# SAMR21_Xplained_Pro_Target_MCU.net
KiCad netlist of a schematic drawn in Altium Designer
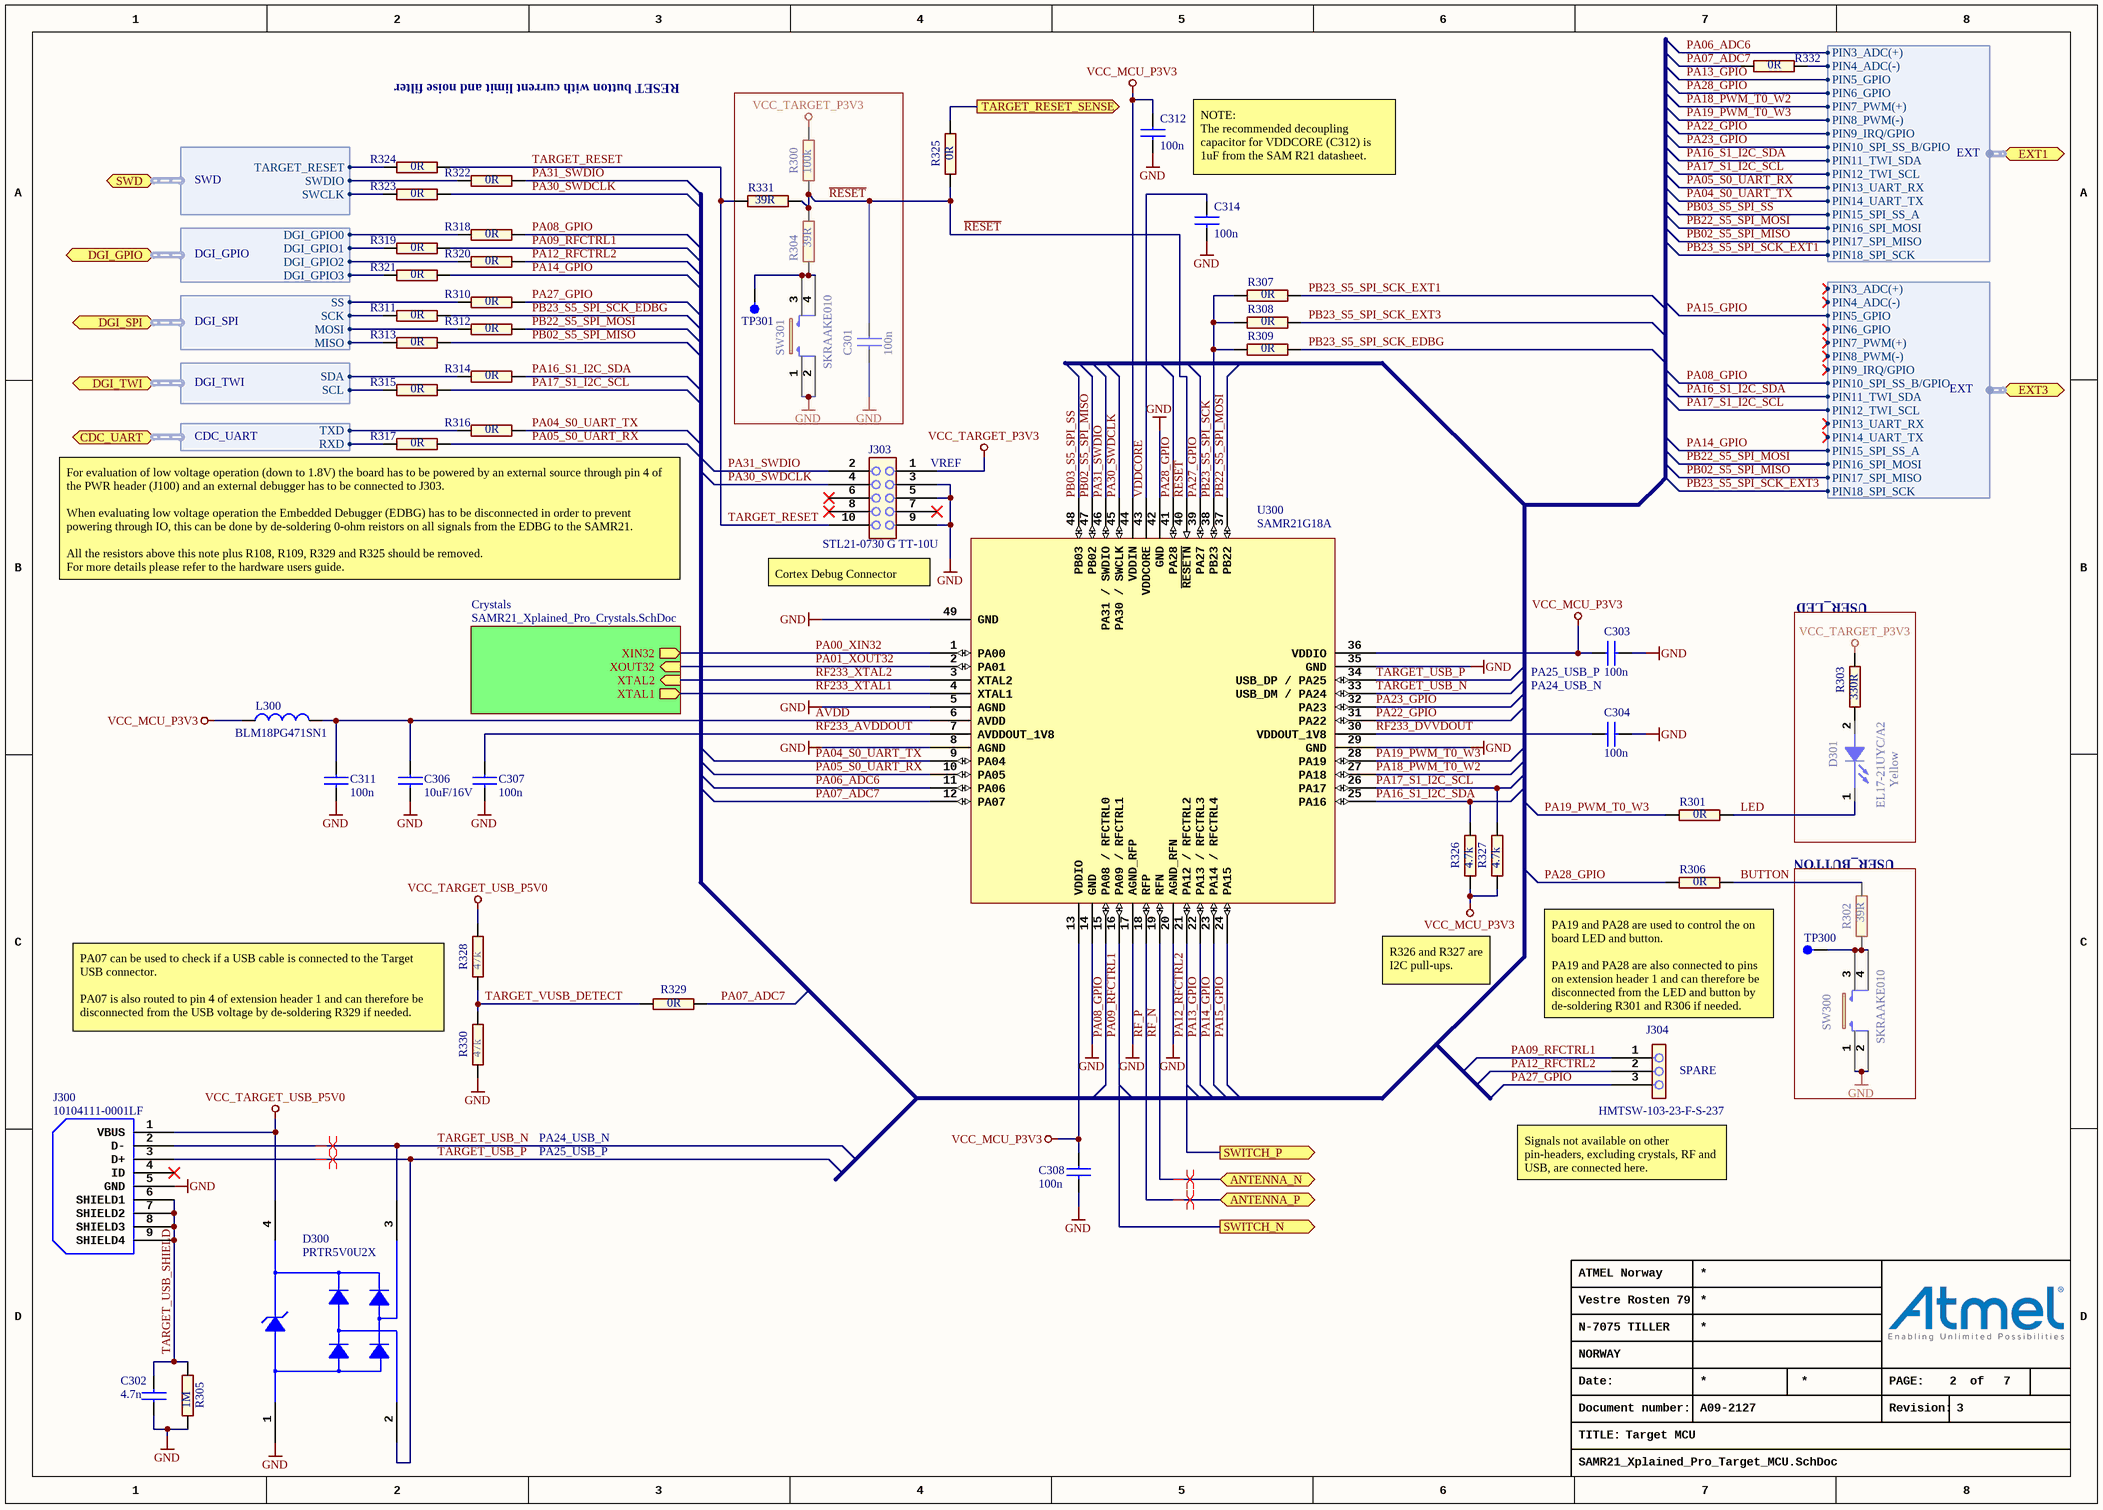
[diagram p0: SAMR21_Xplained_Pro_Target_MCU.SchDoc]

(export (version "E")
  (design (tool "Eeschema 10.0.6"))
  (components
    (comp (ref "C301")
      (value "100n")
      (footprint "AP1-00053")
      (description "Ceramic capacitor, SMD 0402, X7R, 16V, +/-10%")
      (fields (field (name "TOLERANCE") "16V, +/-10%") (field (name "MANUFACTURER") "Kemet"))
      (libsource (lib "AltiumDbLib") (part "CAP-NONPOL"))
    )
    (comp (ref "C302")
      (value "4.7n")
      (footprint "AP1-00053")
      (description "Ceramic capacitor, SMD 0402, X7R, 25V, +/-10%")
      (fields (field (name "TOLERANCE") "25V, +/-10%") (field (name "Comment") "CAP-NONPOL"))
      (libsource (lib "AltiumDbLib") (part "CAP-NONPOL"))
    )
    (comp (ref "C303")
      (value "100n")
      (footprint "AP1-00001")
      (description "Ceramic capacitor, SMD 0402, X7R, 16V, +/-10%")
      (fields (field (name "TOLERANCE") "16V, +/-10%") (field (name "MANUFACTURER") "Kemet"))
      (libsource (lib "AltiumDbLib") (part "CAP-NONPOL"))
    )
    (comp (ref "C304")
      (value "100n")
      (footprint "AP1-00001")
      (description "Ceramic capacitor, SMD 0402, X7R, 16V, +/-10%")
      (fields (field (name "TOLERANCE") "16V, +/-10%") (field (name "MANUFACTURER") "Kemet"))
      (libsource (lib "AltiumDbLib") (part "CAP-NONPOL"))
    )
    (comp (ref "C306")
      (value "10uF/16V")
      (footprint "AP1-00039")
      (description "Ceramic capacitor, SMD 0603, X5R, 16V, 10UF ± 20% (High Density)")
      (fields (field (name "MANUFACTURER") "Taiyo Yuden") (field (name "MPN") "EMK107BBJ106MA-T"))
      (libsource (lib "AltiumDbLib") (part "CAP-NONPOL"))
    )
    (comp (ref "C307")
      (value "100n")
      (footprint "AP1-00001")
      (description "Ceramic capacitor, SMD 0402, X7R, 16V, +/-10%")
      (fields (field (name "TOLERANCE") "16V, +/-10%") (field (name "MANUFACTURER") "Kemet"))
      (libsource (lib "AltiumDbLib") (part "CAP-NONPOL"))
    )
    (comp (ref "C308")
      (value "100n")
      (footprint "AP1-00001")
      (description "Ceramic capacitor, SMD 0402, X7R, 16V, +/-10%")
      (fields (field (name "TOLERANCE") "16V, +/-10%") (field (name "MANUFACTURER") "Kemet"))
      (libsource (lib "AltiumDbLib") (part "CAP-NONPOL"))
    )
    (comp (ref "C311")
      (value "100n")
      (footprint "AP1-00001")
      (description "Ceramic capacitor, SMD 0402, X7R, 16V, +/-10%")
      (fields (field (name "TOLERANCE") "16V, +/-10%") (field (name "MANUFACTURER") "Kemet"))
      (libsource (lib "AltiumDbLib") (part "CAP-NONPOL"))
    )
    (comp (ref "C312")
      (value "100n")
      (footprint "AP1-00001")
      (description "Ceramic capacitor, SMD 0402, X7R, 16V, +/-10%")
      (fields (field (name "TOLERANCE") "16V, +/-10%") (field (name "MANUFACTURER") "Kemet"))
      (libsource (lib "AltiumDbLib") (part "CAP-NONPOL"))
    )
    (comp (ref "C314")
      (value "100n")
      (footprint "AP1-00001")
      (description "Ceramic capacitor, SMD 0402, X7R, 16V, +/-10%")
      (fields (field (name "TOLERANCE") "16V, +/-10%") (field (name "MANUFACTURER") "Kemet"))
      (libsource (lib "AltiumDbLib") (part "CAP-NONPOL"))
    )
    (comp (ref "D300")
      (value "PRTR5V0U2X")
      (footprint "AP4-00001")
      (description "Double rail-to-rail USB ESD protection diode")
      (fields (field (name "MANUFACTURER") "Philips"))
      (libsource (lib "AltiumDbLib") (part "PRTR5V0U2X"))
    )
    (comp (ref "D301")
      (value "Yellow")
      (footprint "AP4-00013")
      (description "LED, Yellow, Wave length=591nm, SMD 0805, ±70°")
      (fields
        (field (name "ALTIUM_VALUE") "EL17-21UYC/A2")
        (field (name "MANUFACTURER") "Everlight")
        (field (name "MPN") "17-21UYC/S530-A3/TR8")
      )
      (libsource (lib "AltiumDbLib") (part "LED_12"))
    )
    (comp (ref "J300")
      (value "10104111-0001LF")
      (footprint "AP8-00604")
      (description "Micro USB AB Connector")
      (fields (field (name "MANUFACTURER") "FCI") (field (name "Comment") "USB_AB"))
      (libsource (lib "AltiumDbLib") (part "USB_AB"))
    )
    (comp (ref "J303")
      (value "HEADER 2x5")
      (footprint "AP8-00257")
      (description "2x5 pin header, 1.27mm pitch, THM")
      (fields (field (name "MANUFACTURER") "Garry") (field (name "MPN") "STL21-0730 G TT-10U"))
      (libsource (lib "AltiumDbLib") (part "HEADER 2x5"))
    )
    (comp (ref "J304")
      (value "HMTSW-103-23-F-S-237")
      (footprint "AP8-00745")
      (description "1x3 pin header, 2.54mm pitch, Pin-in-Paste THM, 1mm hole")
      (fields (field (name "Comment") "HEADER 1x3"))
      (libsource (lib "AltiumDbLib") (part "HEADER 1x3"))
    )
    (comp (ref "L300")
      (value "BLM18PG471SN1")
      (footprint "AP3-00005")
      (description "SMD RF inductor 0603. Z=470Ohm (@100MHz), Max R(dc)=0.65Ohm, Max current=1A")
      (fields (field (name "TOLERANCE") "±25%") (field (name "MANUFACTURER") "Murata"))
      (libsource (lib "AltiumDbLib") (part "INDUCTOR"))
    )
    (comp (ref "R300")
      (value "100k")
      (footprint "AP2-00000")
      (description "Thick film resistor, SMD 0402, 1/16W, 1%")
      (fields (field (name "TOLERANCE") "1 %") (field (name "Comment") "R2"))
      (libsource (lib "") (part "R2_1"))
    )
    (comp (ref "R301")
      (value "0R")
      (footprint "AP2-00000")
      (description "RES 0.0 OHM 1/16W 0402 SMD")
      (fields (field (name "TOLERANCE") "1 %") (field (name "MPN") "RMCF0402ZT0R00"))
      (libsource (lib "AltiumDbLib") (part "R2"))
    )
    (comp (ref "R302")
      (value "39R")
      (footprint "AP2-00011")
      (description "Thick film resistor, SMD 0402, 1/16W, 1%")
      (fields (field (name "TOLERANCE") "1 %") (field (name "Comment") "R2"))
      (libsource (lib "") (part "R2_3"))
    )
    (comp (ref "R303")
      (value "330R")
      (footprint "AP2-00000")
      (description "Thick film resistor, SMD 0402, 1/16W, 1%")
      (fields (field (name "TOLERANCE") "1 %") (field (name "Comment") "R2"))
      (libsource (lib "") (part "R2_1"))
    )
    (comp (ref "R304")
      (value "39R")
      (footprint "AP2-00011")
      (description "Thick film resistor, SMD 0402, 1/16W, 1%")
      (fields (field (name "TOLERANCE") "1 %") (field (name "Comment") "R2"))
      (libsource (lib "") (part "R2_3"))
    )
    (comp (ref "R305")
      (value "1M")
      (footprint "AP2-00011")
      (description "Thick film resistor, SMD 0402, 1/16W, 1%")
      (fields (field (name "TOLERANCE") "1 %") (field (name "MANUFACTURER") "KOA"))
      (libsource (lib "") (part "R2_3"))
    )
    (comp (ref "R306")
      (value "0R")
      (footprint "AP2-00000")
      (description "RES 0.0 OHM 1/16W 0402 SMD")
      (fields (field (name "TOLERANCE") "1 %") (field (name "MPN") "RMCF0402ZT0R00"))
      (libsource (lib "AltiumDbLib") (part "R2"))
    )
    (comp (ref "R307")
      (value "0R")
      (footprint "AP2-00000")
      (description "RES 0.0 OHM 1/16W 0402 SMD")
      (fields (field (name "TOLERANCE") "1 %") (field (name "MPN") "RMCF0402ZT0R00"))
      (libsource (lib "AltiumDbLib") (part "R2"))
    )
    (comp (ref "R308")
      (value "0R")
      (footprint "AP2-00000")
      (description "RES 0.0 OHM 1/16W 0402 SMD")
      (fields (field (name "TOLERANCE") "1 %") (field (name "MPN") "RMCF0402ZT0R00"))
      (libsource (lib "AltiumDbLib") (part "R2"))
    )
    (comp (ref "R309")
      (value "0R")
      (footprint "AP2-00000")
      (description "RES 0.0 OHM 1/16W 0402 SMD")
      (fields (field (name "TOLERANCE") "1 %") (field (name "MPN") "RMCF0402ZT0R00"))
      (libsource (lib "AltiumDbLib") (part "R2"))
    )
    (comp (ref "R310")
      (value "0R")
      (footprint "AP2-00000")
      (description "RES 0.0 OHM 1/16W 0402 SMD")
      (fields (field (name "TOLERANCE") "1 %") (field (name "MPN") "RMCF0402ZT0R00"))
      (libsource (lib "AltiumDbLib") (part "R2"))
    )
    (comp (ref "R311")
      (value "0R")
      (footprint "AP2-00000")
      (description "RES 0.0 OHM 1/16W 0402 SMD")
      (fields (field (name "TOLERANCE") "1 %") (field (name "MPN") "RMCF0402ZT0R00"))
      (libsource (lib "AltiumDbLib") (part "R2"))
    )
    (comp (ref "R312")
      (value "0R")
      (footprint "AP2-00000")
      (description "RES 0.0 OHM 1/16W 0402 SMD")
      (fields (field (name "TOLERANCE") "1 %") (field (name "MPN") "RMCF0402ZT0R00"))
      (libsource (lib "AltiumDbLib") (part "R2"))
    )
    (comp (ref "R313")
      (value "0R")
      (footprint "AP2-00000")
      (description "RES 0.0 OHM 1/16W 0402 SMD")
      (fields (field (name "TOLERANCE") "1 %") (field (name "MPN") "RMCF0402ZT0R00"))
      (libsource (lib "AltiumDbLib") (part "R2"))
    )
    (comp (ref "R314")
      (value "0R")
      (footprint "AP2-00000")
      (description "RES 0.0 OHM 1/16W 0402 SMD")
      (fields (field (name "TOLERANCE") "1 %") (field (name "MPN") "RMCF0402ZT0R00"))
      (libsource (lib "AltiumDbLib") (part "R2"))
    )
    (comp (ref "R315")
      (value "0R")
      (footprint "AP2-00000")
      (description "RES 0.0 OHM 1/16W 0402 SMD")
      (fields (field (name "TOLERANCE") "1 %") (field (name "MPN") "RMCF0402ZT0R00"))
      (libsource (lib "AltiumDbLib") (part "R2"))
    )
    (comp (ref "R316")
      (value "0R")
      (footprint "AP2-00000")
      (description "RES 0.0 OHM 1/16W 0402 SMD")
      (fields (field (name "TOLERANCE") "1 %") (field (name "MPN") "RMCF0402ZT0R00"))
      (libsource (lib "AltiumDbLib") (part "R2"))
    )
    (comp (ref "R317")
      (value "0R")
      (footprint "AP2-00000")
      (description "RES 0.0 OHM 1/16W 0402 SMD")
      (fields (field (name "TOLERANCE") "1 %") (field (name "MPN") "RMCF0402ZT0R00"))
      (libsource (lib "AltiumDbLib") (part "R2"))
    )
    (comp (ref "R318")
      (value "0R")
      (footprint "AP2-00000")
      (description "RES 0.0 OHM 1/16W 0402 SMD")
      (fields (field (name "TOLERANCE") "1 %") (field (name "MPN") "RMCF0402ZT0R00"))
      (libsource (lib "AltiumDbLib") (part "R2"))
    )
    (comp (ref "R319")
      (value "0R")
      (footprint "AP2-00000")
      (description "RES 0.0 OHM 1/16W 0402 SMD")
      (fields (field (name "TOLERANCE") "1 %") (field (name "MPN") "RMCF0402ZT0R00"))
      (libsource (lib "AltiumDbLib") (part "R2"))
    )
    (comp (ref "R320")
      (value "0R")
      (footprint "AP2-00000")
      (description "RES 0.0 OHM 1/16W 0402 SMD")
      (fields (field (name "TOLERANCE") "1 %") (field (name "MPN") "RMCF0402ZT0R00"))
      (libsource (lib "AltiumDbLib") (part "R2"))
    )
    (comp (ref "R321")
      (value "0R")
      (footprint "AP2-00000")
      (description "RES 0.0 OHM 1/16W 0402 SMD")
      (fields (field (name "TOLERANCE") "1 %") (field (name "MPN") "RMCF0402ZT0R00"))
      (libsource (lib "AltiumDbLib") (part "R2"))
    )
    (comp (ref "R322")
      (value "0R")
      (footprint "AP2-00000")
      (description "RES 0.0 OHM 1/16W 0402 SMD")
      (fields (field (name "TOLERANCE") "1 %") (field (name "MPN") "RMCF0402ZT0R00"))
      (libsource (lib "AltiumDbLib") (part "R2"))
    )
    (comp (ref "R323")
      (value "0R")
      (footprint "AP2-00000")
      (description "RES 0.0 OHM 1/16W 0402 SMD")
      (fields (field (name "TOLERANCE") "1 %") (field (name "MPN") "RMCF0402ZT0R00"))
      (libsource (lib "AltiumDbLib") (part "R2"))
    )
    (comp (ref "R324")
      (value "0R")
      (footprint "AP2-00000")
      (description "RES 0.0 OHM 1/16W 0402 SMD")
      (fields (field (name "TOLERANCE") "1 %") (field (name "MPN") "RMCF0402ZT0R00"))
      (libsource (lib "AltiumDbLib") (part "R2"))
    )
    (comp (ref "R325")
      (value "0R")
      (footprint "AP2-00000")
      (description "RES 0.0 OHM 1/16W 0402 SMD")
      (fields (field (name "TOLERANCE") "1 %") (field (name "MPN") "RMCF0402ZT0R00"))
      (libsource (lib "") (part "R2_1"))
    )
    (comp (ref "R326")
      (value "4.7k")
      (footprint "AP2-00000")
      (description "Thick film resistor, SMD 0402, 1/16W, 1%")
      (fields (field (name "TOLERANCE") "1 %") (field (name "Comment") "R2"))
      (libsource (lib "") (part "R2_1"))
    )
    (comp (ref "R327")
      (value "4.7k")
      (footprint "AP2-00000")
      (description "Thick film resistor, SMD 0402, 1/16W, 1%")
      (fields (field (name "TOLERANCE") "1 %") (field (name "Comment") "R2"))
      (libsource (lib "") (part "R2_1"))
    )
    (comp (ref "R328")
      (value "47k")
      (footprint "AP2-00000")
      (description "Thick film resistor, SMD 0402, 1/16W, 1%")
      (fields (field (name "TOLERANCE") "1 %") (field (name "Comment") "R2"))
      (libsource (lib "") (part "R2_2"))
    )
    (comp (ref "R329")
      (value "0R")
      (footprint "AP2-00000")
      (description "RES 0.0 OHM 1/16W 0402 SMD")
      (fields (field (name "TOLERANCE") "1 %") (field (name "MPN") "RMCF0402ZT0R00"))
      (libsource (lib "AltiumDbLib") (part "R2"))
    )
    (comp (ref "R330")
      (value "47k")
      (footprint "AP2-00000")
      (description "Thick film resistor, SMD 0402, 1/16W, 1%")
      (fields (field (name "TOLERANCE") "1 %") (field (name "Comment") "R2"))
      (libsource (lib "") (part "R2_2"))
    )
    (comp (ref "R331")
      (value "39R")
      (footprint "AP2-00011")
      (description "Thick film resistor, SMD 0402, 1/16W, 1%")
      (fields (field (name "TOLERANCE") "1 %") (field (name "Comment") "R2"))
      (libsource (lib "") (part "R2_2"))
    )
    (comp (ref "R332")
      (value "0R")
      (footprint "AP2-00000")
      (description "RES 0.0 OHM 1/16W 0402 SMD")
      (fields (field (name "TOLERANCE") "1 %") (field (name "MPN") "RMCF0402ZT0R00"))
      (libsource (lib "AltiumDbLib") (part "R2"))
    )
    (comp (ref "SW300")
      (value "SKRAAKE010")
      (footprint "AP8-00137")
      (description "6.2x6.2 mm SMD tact switch, same as A08-0091 but less force is needed")
      (fields
        (field (name "MANUFACTURER") "ALPS")
        (field (name "Comment") "Can be ordered in low volumes from Mouser")
      )
      (libsource (lib "AltiumDbLib") (part "PUSHBUTTON1"))
    )
    (comp (ref "SW301")
      (value "SKRAAKE010")
      (footprint "AP8-00137")
      (description "6.2x6.2 mm SMD tact switch, same as A08-0091 but less force is needed")
      (fields
        (field (name "MANUFACTURER") "ALPS")
        (field (name "Comment") "Can be ordered in low volumes from Mouser")
      )
      (libsource (lib "AltiumDbLib") (part "PUSHBUTTON1"))
    )
    (comp (ref "TP300")
      (value "TESTPOINT")
      (footprint "AP8-00010")
      (description "Single SMD testpad")
      (libsource (lib "AltiumDbLib") (part "TESTPOINT"))
    )
    (comp (ref "TP301")
      (value "TESTPOINT")
      (footprint "AP8-00010")
      (description "Single SMD testpad")
      (libsource (lib "AltiumDbLib") (part "TESTPOINT"))
    )
    (comp (ref "U300")
      (value "SAMR21G18A")
      (footprint "AP6-00171")
      (description "Atmel 32-bit Cortex M0+ MCU with RF233 SIP.")
      (fields (field (name "MANUFACTURER") "ATMEL") (field (name "MPN") "SAMR21G18A-MUT"))
      (libsource (lib "AltiumDbLib") (part "SAMR21G"))
    )
  )
  (nets
    (net (code "7") (name "/AVDD") (class "Default")
      (node (ref "C306") (pin "1") (pinfunction "1_1") (pintype "passive"))
      (node (ref "C311") (pin "1") (pinfunction "1_1") (pintype "passive"))
      (node (ref "L300") (pin "2") (pinfunction "2_2") (pintype "passive"))
      (node (ref "U300") (pin "6") (pinfunction "AVDD_6") (pintype "power_in"))
    )
    (net (code "8") (name "/BUTTON") (class "Default")
      (node (ref "R302") (pin "2") (pinfunction "2_2") (pintype "passive"))
      (node (ref "R306") (pin "2") (pinfunction "2_2") (pintype "passive"))
    )
    (net (code "9") (name "/DGI_GPIO0") (class "Default")
      (node (ref "R318") (pin "1") (pinfunction "1_1") (pintype "passive"))
    )
    (net (code "10") (name "/DGI_GPIO1") (class "Default")
      (node (ref "R319") (pin "1") (pinfunction "1_1") (pintype "passive"))
    )
    (net (code "11") (name "/DGI_GPIO2") (class "Default")
      (node (ref "R320") (pin "1") (pinfunction "1_1") (pintype "passive"))
    )
    (net (code "12") (name "/DGI_GPIO3") (class "Default")
      (node (ref "R321") (pin "1") (pinfunction "1_1") (pintype "passive"))
    )
    (net (code "13") (name "/LED") (class "Default")
      (node (ref "D301") (pin "1") (pinfunction "CATHODE_1") (pintype "passive"))
      (node (ref "R301") (pin "2") (pinfunction "2_2") (pintype "passive"))
    )
    (net (code "14") (name "/MISO") (class "Default")
      (node (ref "R313") (pin "1") (pinfunction "1_1") (pintype "passive"))
    )
    (net (code "15") (name "/MOSI") (class "Default")
      (node (ref "R312") (pin "1") (pinfunction "1_1") (pintype "passive"))
    )
    (net (code "16") (name "/PA00_XIN32") (class "Default")
      (node (ref "U300") (pin "1") (pinfunction "PA00_1") (pintype "bidirectional"))
    )
    (net (code "17") (name "/PA01_XOUT32") (class "Default")
      (node (ref "U300") (pin "2") (pinfunction "PA01_2") (pintype "bidirectional"))
    )
    (net (code "18") (name "/PA04_S0_UART_TX") (class "Default")
      (node (ref "R316") (pin "2") (pinfunction "2_2") (pintype "passive"))
      (node (ref "U300") (pin "9") (pinfunction "PA04_9") (pintype "bidirectional"))
    )
    (net (code "19") (name "/PA05_S0_UART_RX") (class "Default")
      (node (ref "R317") (pin "2") (pinfunction "2_2") (pintype "passive"))
      (node (ref "U300") (pin "10") (pinfunction "PA05_10") (pintype "bidirectional"))
    )
    (net (code "20") (name "/PA06_ADC6") (class "Default")
      (node (ref "U300") (pin "11") (pinfunction "PA06_11") (pintype "bidirectional"))
    )
    (net (code "21") (name "/PA07_ADC7") (class "Default")
      (node (ref "R329") (pin "2") (pinfunction "2_2") (pintype "passive"))
      (node (ref "R332") (pin "1") (pinfunction "1_1") (pintype "passive"))
      (node (ref "U300") (pin "12") (pinfunction "PA07_12") (pintype "bidirectional"))
    )
    (net (code "22") (name "/PA08_GPIO") (class "Default")
      (node (ref "R318") (pin "2") (pinfunction "2_2") (pintype "passive"))
      (node (ref "U300") (pin "15") (pinfunction "PA08_/_RFCTRL0_15") (pintype "bidirectional"))
    )
    (net (code "23") (name "/PA09_RFCTRL1") (class "Default")
      (node (ref "J304") (pin "1") (pinfunction "1_1") (pintype "passive"))
      (node (ref "R319") (pin "2") (pinfunction "2_2") (pintype "passive"))
      (node (ref "U300") (pin "16") (pinfunction "PA09_/_RFCTRL1_16") (pintype "bidirectional"))
    )
    (net (code "24") (name "/PA12_RFCTRL2") (class "Default")
      (node (ref "J304") (pin "2") (pinfunction "2_2") (pintype "passive"))
      (node (ref "R320") (pin "2") (pinfunction "2_2") (pintype "passive"))
      (node (ref "U300") (pin "21") (pinfunction "PA12_/_RFCTRL2_21") (pintype "bidirectional"))
    )
    (net (code "25") (name "/PA13_GPIO") (class "Default")
      (node (ref "U300") (pin "22") (pinfunction "PA13_/_RFCTRL3_22") (pintype "bidirectional"))
    )
    (net (code "26") (name "/PA14_GPIO") (class "Default")
      (node (ref "R321") (pin "2") (pinfunction "2_2") (pintype "passive"))
      (node (ref "U300") (pin "23") (pinfunction "PA14_/_RFCTRL4_23") (pintype "bidirectional"))
    )
    (net (code "27") (name "/PA15_GPIO") (class "Default")
      (node (ref "U300") (pin "24") (pinfunction "PA15_24") (pintype "bidirectional"))
    )
    (net (code "28") (name "/PA16_S1_I2C_SDA") (class "Default")
      (node (ref "R314") (pin "2") (pinfunction "2_2") (pintype "passive"))
      (node (ref "R326") (pin "2") (pinfunction "2_2") (pintype "passive"))
      (node (ref "U300") (pin "25") (pinfunction "PA16_25") (pintype "bidirectional"))
    )
    (net (code "29") (name "/PA17_S1_I2C_SCL") (class "Default")
      (node (ref "R315") (pin "2") (pinfunction "2_2") (pintype "passive"))
      (node (ref "R327") (pin "2") (pinfunction "2_2") (pintype "passive"))
      (node (ref "U300") (pin "26") (pinfunction "PA17_26") (pintype "bidirectional"))
    )
    (net (code "30") (name "/PA18_PWM_T0_W2") (class "Default")
      (node (ref "U300") (pin "27") (pinfunction "PA18_27") (pintype "bidirectional"))
    )
    (net (code "31") (name "/PA19_PWM_T0_W3") (class "Default")
      (node (ref "R301") (pin "1") (pinfunction "1_1") (pintype "passive"))
      (node (ref "U300") (pin "28") (pinfunction "PA19_28") (pintype "bidirectional"))
    )
    (net (code "32") (name "/PA22_GPIO") (class "Default")
      (node (ref "U300") (pin "31") (pinfunction "PA22_31") (pintype "bidirectional"))
    )
    (net (code "33") (name "/PA23_GPIO") (class "Default")
      (node (ref "U300") (pin "32") (pinfunction "PA23_32") (pintype "bidirectional"))
    )
    (net (code "34") (name "/PA27_GPIO") (class "Default")
      (node (ref "J304") (pin "3") (pinfunction "3_3") (pintype "passive"))
      (node (ref "R310") (pin "2") (pinfunction "2_2") (pintype "passive"))
      (node (ref "U300") (pin "39") (pinfunction "PA27_39") (pintype "bidirectional"))
    )
    (net (code "35") (name "/PA28_GPIO") (class "Default")
      (node (ref "R306") (pin "1") (pinfunction "1_1") (pintype "passive"))
      (node (ref "U300") (pin "41") (pinfunction "PA28_41") (pintype "bidirectional"))
    )
    (net (code "36") (name "/PA30_SWDCLK") (class "Default")
      (node (ref "J303") (pin "4") (pinfunction "4_4") (pintype "passive"))
      (node (ref "R323") (pin "2") (pinfunction "2_2") (pintype "passive"))
      (node (ref "U300") (pin "45") (pinfunction "PA30_/_SWCLK_45") (pintype "bidirectional"))
    )
    (net (code "37") (name "/PA31_SWDIO") (class "Default")
      (node (ref "J303") (pin "2") (pinfunction "2_2") (pintype "passive"))
      (node (ref "R322") (pin "2") (pinfunction "2_2") (pintype "passive"))
      (node (ref "U300") (pin "46") (pinfunction "PA31_/_SWDIO_46") (pintype "bidirectional"))
    )
    (net (code "38") (name "/PB02_S5_SPI_MISO") (class "Default")
      (node (ref "R313") (pin "2") (pinfunction "2_2") (pintype "passive"))
      (node (ref "U300") (pin "47") (pinfunction "PB02_47") (pintype "bidirectional"))
    )
    (net (code "39") (name "/PB03_S5_SPI_SS") (class "Default")
      (node (ref "U300") (pin "48") (pinfunction "PB03_48") (pintype "bidirectional"))
    )
    (net (code "40") (name "/PB22_S5_SPI_MOSI") (class "Default")
      (node (ref "R312") (pin "2") (pinfunction "2_2") (pintype "passive"))
      (node (ref "U300") (pin "37") (pinfunction "PB22_37") (pintype "bidirectional"))
    )
    (net (code "41") (name "/PB23_S5_SPI_SCK") (class "Default")
      (node (ref "R307") (pin "1") (pinfunction "1_1") (pintype "passive"))
      (node (ref "R308") (pin "1") (pinfunction "1_1") (pintype "passive"))
      (node (ref "R309") (pin "1") (pinfunction "1_1") (pintype "passive"))
      (node (ref "U300") (pin "38") (pinfunction "PB23_38") (pintype "bidirectional"))
    )
    (net (code "42") (name "/PB23_S5_SPI_SCK_EDBG") (class "Default")
      (node (ref "R309") (pin "2") (pinfunction "2_2") (pintype "passive"))
      (node (ref "R311") (pin "2") (pinfunction "2_2") (pintype "passive"))
    )
    (net (code "43") (name "/PB23_S5_SPI_SCK_EXT1") (class "Default")
      (node (ref "R307") (pin "2") (pinfunction "2_2") (pintype "passive"))
    )
    (net (code "44") (name "/PB23_S5_SPI_SCK_EXT3") (class "Default")
      (node (ref "R308") (pin "2") (pinfunction "2_2") (pintype "passive"))
    )
    (net (code "45") (name "/RF233_AVDDOUT") (class "Default")
      (node (ref "C307") (pin "1") (pinfunction "1_1") (pintype "passive"))
      (node (ref "U300") (pin "7") (pinfunction "AVDDOUT_1V8_7") (pintype "power_in"))
    )
    (net (code "46") (name "/RF233_DVVDOUT") (class "Default")
      (node (ref "C304") (pin "1") (pinfunction "1_1") (pintype "passive"))
      (node (ref "U300") (pin "30") (pinfunction "VDDOUT_1V8_30") (pintype "power_in"))
    )
    (net (code "47") (name "/RF233_XTAL1") (class "Default")
      (node (ref "U300") (pin "4") (pinfunction "XTAL1_4") (pintype "passive"))
    )
    (net (code "48") (name "/RF233_XTAL2") (class "Default")
      (node (ref "U300") (pin "3") (pinfunction "XTAL2_3") (pintype "passive"))
    )
    (net (code "49") (name "/RF_N") (class "Default")
      (node (ref "U300") (pin "19") (pinfunction "RFN_19") (pintype "bidirectional"))
    )
    (net (code "50") (name "/RF_P") (class "Default")
      (node (ref "U300") (pin "18") (pinfunction "RFP_18") (pintype "bidirectional"))
    )
    (net (code "51") (name "/RXD") (class "Default")
      (node (ref "R317") (pin "1") (pinfunction "1_1") (pintype "passive"))
    )
    (net (code "52") (name "/SCK") (class "Default")
      (node (ref "R311") (pin "1") (pinfunction "1_1") (pintype "passive"))
    )
    (net (code "53") (name "/SCL") (class "Default")
      (node (ref "R315") (pin "1") (pinfunction "1_1") (pintype "passive"))
    )
    (net (code "54") (name "/SDA") (class "Default")
      (node (ref "R314") (pin "1") (pinfunction "1_1") (pintype "passive"))
    )
    (net (code "55") (name "/SS") (class "Default")
      (node (ref "R310") (pin "1") (pinfunction "1_1") (pintype "passive"))
    )
    (net (code "56") (name "/SWCLK") (class "Default")
      (node (ref "R323") (pin "1") (pinfunction "1_1") (pintype "passive"))
    )
    (net (code "57") (name "/SWDIO") (class "Default")
      (node (ref "R322") (pin "1") (pinfunction "1_1") (pintype "passive"))
    )
    (net (code "58") (name "/TARGET_RESET") (class "Default")
      (node (ref "J303") (pin "10") (pinfunction "10_10") (pintype "passive"))
      (node (ref "R324") (pin "2") (pinfunction "2_2") (pintype "passive"))
      (node (ref "R331") (pin "1") (pinfunction "1_1") (pintype "passive"))
    )
    (net (code "59") (name "/TARGET_RESET_SENSE") (class "Default")
      (node (ref "R325") (pin "2") (pinfunction "2_2") (pintype "passive"))
    )
    (net (code "60") (name "/TARGET_USB_N") (class "Default")
      (node (ref "D300") (pin "3") (pinfunction "I/O_2_3") (pintype "passive"))
      (node (ref "J300") (pin "2") (pinfunction "D-_2") (pintype "passive"))
      (node (ref "U300") (pin "33") (pinfunction "USB_DM_/_PA24_33") (pintype "bidirectional"))
    )
    (net (code "61") (name "/TARGET_USB_P") (class "Default")
      (node (ref "D300") (pin "2") (pinfunction "I/O_1_2") (pintype "passive"))
      (node (ref "J300") (pin "3") (pinfunction "D+_3") (pintype "passive"))
      (node (ref "U300") (pin "34") (pinfunction "USB_DP_/_PA25_34") (pintype "bidirectional"))
    )
    (net (code "62") (name "/TARGET_USB_SHIELD") (class "Default")
      (node (ref "C302") (pin "2") (pinfunction "2_2") (pintype "passive"))
      (node (ref "J300") (pin "6") (pinfunction "SHIELD1_6") (pintype "passive"))
      (node (ref "J300") (pin "7") (pinfunction "SHIELD2_7") (pintype "passive"))
      (node (ref "J300") (pin "8") (pinfunction "SHIELD3_8") (pintype "passive"))
      (node (ref "J300") (pin "9") (pinfunction "SHIELD4_9") (pintype "passive"))
      (node (ref "R305") (pin "2") (pinfunction "2_2") (pintype "passive"))
    )
    (net (code "63") (name "/TARGET_VUSB_DETECT") (class "Default")
      (node (ref "R328") (pin "1") (pinfunction "1_1") (pintype "passive"))
      (node (ref "R329") (pin "1") (pinfunction "1_1") (pintype "passive"))
      (node (ref "R330") (pin "2") (pinfunction "2_2") (pintype "passive"))
    )
    (net (code "64") (name "/TXD") (class "Default")
      (node (ref "R316") (pin "1") (pinfunction "1_1") (pintype "passive"))
    )
    (net (code "65") (name "/VDDCORE") (class "Default")
      (node (ref "C314") (pin "1") (pinfunction "1_1") (pintype "passive"))
      (node (ref "U300") (pin "43") (pinfunction "VDDCORE_43") (pintype "power_in"))
    )
    (net (code "72") (name "/~{RESET}") (class "Default")
      (node (ref "C301") (pin "1") (pinfunction "1_1") (pintype "passive"))
      (node (ref "R300") (pin "1") (pinfunction "1_1") (pintype "passive"))
      (node (ref "R304") (pin "2") (pinfunction "2_2") (pintype "passive"))
      (node (ref "R325") (pin "1") (pinfunction "1_1") (pintype "passive"))
      (node (ref "R331") (pin "2") (pinfunction "2_2") (pintype "passive"))
      (node (ref "U300") (pin "40") (pinfunction "~{RESETN}_40") (pintype "input"))
    )
    (net (code "73") (name "GND") (class "Default")
      (node (ref "C301") (pin "2") (pinfunction "2_2") (pintype "passive"))
      (node (ref "C302") (pin "1") (pinfunction "1_1") (pintype "passive"))
      (node (ref "C303") (pin "2") (pinfunction "2_2") (pintype "passive"))
      (node (ref "C304") (pin "2") (pinfunction "2_2") (pintype "passive"))
      (node (ref "C306") (pin "2") (pinfunction "2_2") (pintype "passive"))
      (node (ref "C307") (pin "2") (pinfunction "2_2") (pintype "passive"))
      (node (ref "C308") (pin "2") (pinfunction "2_2") (pintype "passive"))
      (node (ref "C311") (pin "2") (pinfunction "2_2") (pintype "passive"))
      (node (ref "C312") (pin "2") (pinfunction "2_2") (pintype "passive"))
      (node (ref "C314") (pin "2") (pinfunction "2_2") (pintype "passive"))
      (node (ref "D300") (pin "1") (pinfunction "GND_1") (pintype "passive"))
      (node (ref "J300") (pin "5") (pinfunction "GND_5") (pintype "passive"))
      (node (ref "J303") (pin "3") (pinfunction "3_3") (pintype "passive"))
      (node (ref "J303") (pin "5") (pinfunction "5_5") (pintype "passive"))
      (node (ref "J303") (pin "9") (pinfunction "9_9") (pintype "passive"))
      (node (ref "R305") (pin "1") (pinfunction "1_1") (pintype "passive"))
      (node (ref "R330") (pin "1") (pinfunction "1_1") (pintype "passive"))
      (node (ref "SW300") (pin "1") (pinfunction "1_1") (pintype "passive"))
      (node (ref "SW300") (pin "2") (pinfunction "2_2") (pintype "passive"))
      (node (ref "SW301") (pin "1") (pinfunction "1_1") (pintype "passive"))
      (node (ref "SW301") (pin "2") (pinfunction "2_2") (pintype "passive"))
      (node (ref "U300") (pin "14") (pinfunction "GND_14") (pintype "power_in"))
      (node (ref "U300") (pin "17") (pinfunction "AGND_RFP_17") (pintype "power_in"))
      (node (ref "U300") (pin "20") (pinfunction "AGND_RFN_20") (pintype "power_in"))
      (node (ref "U300") (pin "29") (pinfunction "GND_29") (pintype "power_in"))
      (node (ref "U300") (pin "35") (pinfunction "GND_35") (pintype "power_in"))
      (node (ref "U300") (pin "42") (pinfunction "GND_42") (pintype "power_in"))
      (node (ref "U300") (pin "49") (pinfunction "GND_49") (pintype "power_in"))
      (node (ref "U300") (pin "5") (pinfunction "AGND_5") (pintype "power_in"))
      (node (ref "U300") (pin "8") (pinfunction "AGND_8") (pintype "power_in"))
    )
    (net (code "74") (name "Net-(D301-ANODE)") (class "Default")
      (node (ref "D301") (pin "2") (pinfunction "ANODE_2") (pintype "passive"))
      (node (ref "R303") (pin "1") (pinfunction "1_1") (pintype "passive"))
    )
    (net (code "75") (name "Net-(R302-Pad1)") (class "Default")
      (node (ref "R302") (pin "1") (pinfunction "1_1") (pintype "passive"))
      (node (ref "SW300") (pin "3") (pinfunction "3_3") (pintype "passive"))
      (node (ref "SW300") (pin "4") (pinfunction "4_4") (pintype "passive"))
      (node (ref "TP300") (pin "1") (pinfunction "1_1") (pintype "passive"))
    )
    (net (code "76") (name "Net-(R304-Pad1)") (class "Default")
      (node (ref "R304") (pin "1") (pinfunction "1_1") (pintype "passive"))
      (node (ref "SW301") (pin "3") (pinfunction "3_3") (pintype "passive"))
      (node (ref "SW301") (pin "4") (pinfunction "4_4") (pintype "passive"))
      (node (ref "TP301") (pin "1") (pinfunction "1_1") (pintype "passive"))
    )
    (net (code "77") (name "VCC_MCU_P3V3") (class "Default")
      (node (ref "C303") (pin "1") (pinfunction "1_1") (pintype "passive"))
      (node (ref "C308") (pin "1") (pinfunction "1_1") (pintype "passive"))
      (node (ref "C312") (pin "1") (pinfunction "1_1") (pintype "passive"))
      (node (ref "L300") (pin "1") (pinfunction "1_1") (pintype "passive"))
      (node (ref "R326") (pin "1") (pinfunction "1_1") (pintype "passive"))
      (node (ref "R327") (pin "1") (pinfunction "1_1") (pintype "passive"))
      (node (ref "U300") (pin "13") (pinfunction "VDDIO_13") (pintype "power_in"))
      (node (ref "U300") (pin "36") (pinfunction "VDDIO_36") (pintype "power_in"))
      (node (ref "U300") (pin "44") (pinfunction "VDDIN_44") (pintype "power_in"))
    )
    (net (code "78") (name "VCC_TARGET_P3V3") (class "Default")
      (node (ref "J303") (pin "1") (pinfunction "1_1") (pintype "passive"))
      (node (ref "R300") (pin "2") (pinfunction "2_2") (pintype "passive"))
      (node (ref "R303") (pin "2") (pinfunction "2_2") (pintype "passive"))
    )
    (net (code "79") (name "VCC_TARGET_USB_P5V0") (class "Default")
      (node (ref "D300") (pin "4") (pinfunction "VCC_4") (pintype "passive"))
      (node (ref "J300") (pin "1") (pinfunction "VBUS_1") (pintype "passive"))
      (node (ref "R328") (pin "2") (pinfunction "2_2") (pintype "passive"))
    )
    (net (code "80") (name "unconnected-(J300-ID-Pad4)") (class "Default")
      (node (ref "J300") (pin "4") (pinfunction "ID_4") (pintype "passive+no_connect"))
    )
    (net (code "81") (name "unconnected-(J303-Pad6)") (class "Default")
      (node (ref "J303") (pin "6") (pinfunction "6_6") (pintype "passive+no_connect"))
    )
    (net (code "82") (name "unconnected-(J303-Pad7)") (class "Default")
      (node (ref "J303") (pin "7") (pinfunction "7_7") (pintype "passive+no_connect"))
    )
    (net (code "83") (name "unconnected-(J303-Pad8)") (class "Default")
      (node (ref "J303") (pin "8") (pinfunction "8_8") (pintype "passive+no_connect"))
    )
    (net (code "84") (name "unconnected-(R324-Pad1)") (class "Default")
      (node (ref "R324") (pin "1") (pinfunction "1_1") (pintype "passive"))
    )
    (net (code "85") (name "unconnected-(R332-Pad2)") (class "Default")
      (node (ref "R332") (pin "2") (pinfunction "2_2") (pintype "passive"))
    )
  )
)
